# ServoDrivers.net
KiCad netlist of a schematic drawn in Altium Designer
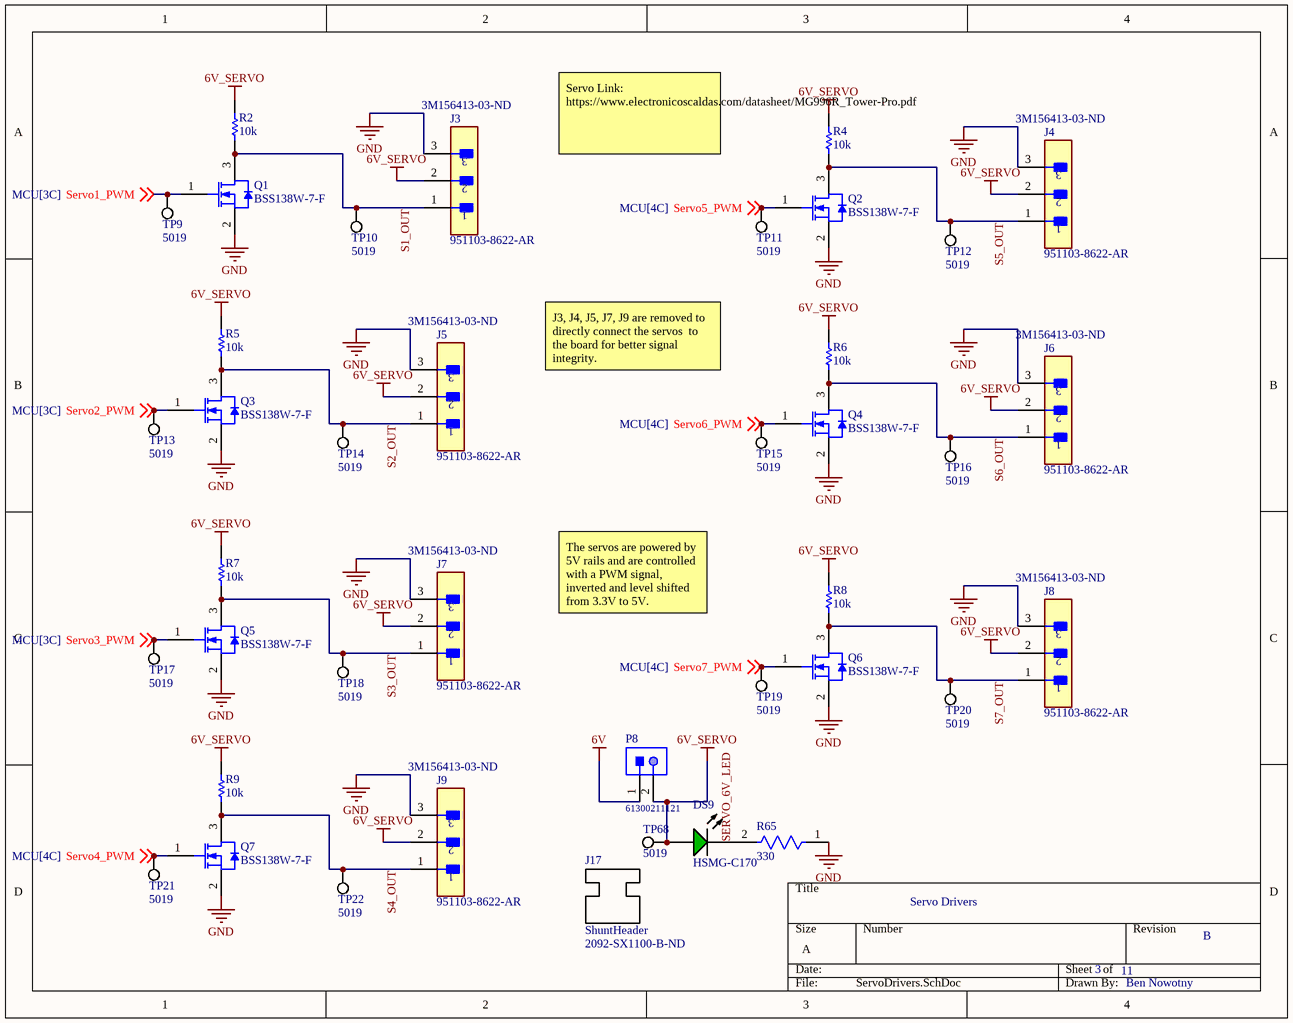
[diagram p0: ServoDrivers.SchDoc]

(export (version "E")
  (design (tool "Eeschema 10.0.6"))
  (components
    (comp (ref "DS9")
      (value "HSMG-C170")
      (footprint "AVAG-HSMX-C170_V")
      (description "Chip LED, Green, 2.2 V, -40 to 85 degC, 2-Pin SMD, Pb-Free, Tape and Reel")
      (fields (field (name "MANUFACTURER") "Avago"))
      (libsource (lib "Altium Content Vault") (part "LED_GREEN_A1K2-2"))
    )
    (comp (ref "J3")
      (value "951103-8622-AR")
      (footprint "FP-951103-8622-AR-MFG")
      (description "CONN HEADER VERT 3POS 2MM")
      (fields
        (field (name "OCTOPART") "https://octopart.com/951103-8622-ar-3m-14400669")
        (field (name "MANUFACTURER") "3M")
        (field (name "SUPPLIER PART NUMBER 1") "3M156413-03-ND")
      )
      (libsource (lib "Altium Content Vault") (part "0d3f023dd272f625e17a2be33dea85f"))
    )
    (comp (ref "J4")
      (value "951103-8622-AR")
      (footprint "FP-951103-8622-AR-MFG")
      (description "CONN HEADER VERT 3POS 2MM")
      (fields
        (field (name "OCTOPART") "https://octopart.com/951103-8622-ar-3m-14400669")
        (field (name "MANUFACTURER") "3M")
        (field (name "SUPPLIER PART NUMBER 1") "3M156413-03-ND")
      )
      (libsource (lib "Altium Content Vault") (part "0d3f023dd272f625e17a2be33dea85f"))
    )
    (comp (ref "J5")
      (value "951103-8622-AR")
      (footprint "FP-951103-8622-AR-MFG")
      (description "CONN HEADER VERT 3POS 2MM")
      (fields
        (field (name "OCTOPART") "https://octopart.com/951103-8622-ar-3m-14400669")
        (field (name "MANUFACTURER") "3M")
        (field (name "SUPPLIER PART NUMBER 1") "3M156413-03-ND")
      )
      (libsource (lib "Altium Content Vault") (part "0d3f023dd272f625e17a2be33dea85f"))
    )
    (comp (ref "J6")
      (value "951103-8622-AR")
      (footprint "FP-951103-8622-AR-MFG")
      (description "CONN HEADER VERT 3POS 2MM")
      (fields
        (field (name "OCTOPART") "https://octopart.com/951103-8622-ar-3m-14400669")
        (field (name "MANUFACTURER") "3M")
        (field (name "SUPPLIER PART NUMBER 1") "3M156413-03-ND")
      )
      (libsource (lib "Altium Content Vault") (part "0d3f023dd272f625e17a2be33dea85f"))
    )
    (comp (ref "J7")
      (value "951103-8622-AR")
      (footprint "FP-951103-8622-AR-MFG")
      (description "CONN HEADER VERT 3POS 2MM")
      (fields
        (field (name "OCTOPART") "https://octopart.com/951103-8622-ar-3m-14400669")
        (field (name "MANUFACTURER") "3M")
        (field (name "SUPPLIER PART NUMBER 1") "3M156413-03-ND")
      )
      (libsource (lib "Altium Content Vault") (part "0d3f023dd272f625e17a2be33dea85f"))
    )
    (comp (ref "J8")
      (value "951103-8622-AR")
      (footprint "FP-951103-8622-AR-MFG")
      (description "CONN HEADER VERT 3POS 2MM")
      (fields
        (field (name "OCTOPART") "https://octopart.com/951103-8622-ar-3m-14400669")
        (field (name "MANUFACTURER") "3M")
        (field (name "SUPPLIER PART NUMBER 1") "3M156413-03-ND")
      )
      (libsource (lib "Altium Content Vault") (part "0d3f023dd272f625e17a2be33dea85f"))
    )
    (comp (ref "J9")
      (value "951103-8622-AR")
      (footprint "FP-951103-8622-AR-MFG")
      (description "CONN HEADER VERT 3POS 2MM")
      (fields
        (field (name "OCTOPART") "https://octopart.com/951103-8622-ar-3m-14400669")
        (field (name "MANUFACTURER") "3M")
        (field (name "SUPPLIER PART NUMBER 1") "3M156413-03-ND")
      )
      (libsource (lib "Altium Content Vault") (part "0d3f023dd272f625e17a2be33dea85f"))
    )
    (comp (ref "J17")
      (value "ShuntHeader")
      (description "Conn Mini Shunt 2 POS 2.54mm Black Cable Mount")
      (fields
        (field (name "MANUFACTURER") "Kycon")
        (field (name "MANUFACTURER PART NUMBER") "SX1100-B")
        (field (name "SUPPLIER PART NUMBER 1") "2092-SX1100-B-ND")
      )
      (libsource (lib "CustomSchematics") (part "ShuntHeader"))
    )
    (comp (ref "P8")
      (value "61300211121")
      (footprint "61300211121")
      (description "THT Vertical Pin Header WR-PHD, Pitch 2.54 mm, Single Row, 2 pins")
      (fields (field (name "MANUFACTURER") "Wurth Elektronik") (field (name "PUBLISHER") "WurthElektronik"))
      (libsource (lib "Altium Content Vault") (part "WE-CN-1P-M-R2"))
    )
    (comp (ref "Q1")
      (value "BSS138W-7-F")
      (footprint "DIOD-SOT323-3_V")
      (fields (field (name "MANUFACTURER") "DiodesIncorporated") (field (name "VOLTAGE") "50V"))
      (libsource (lib "Altium Content Vault") (part "NEMOS-GSD-3"))
    )
    (comp (ref "Q2")
      (value "BSS138W-7-F")
      (footprint "DIOD-SOT323-3_V")
      (fields (field (name "MANUFACTURER") "DiodesIncorporated") (field (name "VOLTAGE") "50V"))
      (libsource (lib "Altium Content Vault") (part "NEMOS-GSD-3"))
    )
    (comp (ref "Q3")
      (value "BSS138W-7-F")
      (footprint "DIOD-SOT323-3_V")
      (fields (field (name "MANUFACTURER") "DiodesIncorporated") (field (name "VOLTAGE") "50V"))
      (libsource (lib "Altium Content Vault") (part "NEMOS-GSD-3"))
    )
    (comp (ref "Q4")
      (value "BSS138W-7-F")
      (footprint "DIOD-SOT323-3_V")
      (fields (field (name "MANUFACTURER") "DiodesIncorporated") (field (name "VOLTAGE") "50V"))
      (libsource (lib "Altium Content Vault") (part "NEMOS-GSD-3"))
    )
    (comp (ref "Q5")
      (value "BSS138W-7-F")
      (footprint "DIOD-SOT323-3_V")
      (fields (field (name "MANUFACTURER") "DiodesIncorporated") (field (name "VOLTAGE") "50V"))
      (libsource (lib "Altium Content Vault") (part "NEMOS-GSD-3"))
    )
    (comp (ref "Q6")
      (value "BSS138W-7-F")
      (footprint "DIOD-SOT323-3_V")
      (fields (field (name "MANUFACTURER") "DiodesIncorporated") (field (name "VOLTAGE") "50V"))
      (libsource (lib "Altium Content Vault") (part "NEMOS-GSD-3"))
    )
    (comp (ref "Q7")
      (value "BSS138W-7-F")
      (footprint "DIOD-SOT323-3_V")
      (fields (field (name "MANUFACTURER") "DiodesIncorporated") (field (name "VOLTAGE") "50V"))
      (libsource (lib "Altium Content Vault") (part "NEMOS-GSD-3"))
    )
    (comp (ref "R2")
      (value "10k")
      (footprint "RESC2013X60X35NL10T20")
      (description "Chip Resistor, 10 KOhm, +/- 1%, 0.125 W, -55 to 155 degC, 0805 (2012 Metric), RoHS, Tape and Reel")
      (fields
        (field (name "MANUFACTURER") "Yageo")
        (field (name "MANUFACTURER PART NUMBER") "RC0805FR-0710KL")
      )
      (libsource (lib "Altium Content Vault") (part "RES-2"))
    )
    (comp (ref "R4")
      (value "10k")
      (footprint "RESC2013X60X35NL10T20")
      (description "Chip Resistor, 10 KOhm, +/- 1%, 0.125 W, -55 to 155 degC, 0805 (2012 Metric), RoHS, Tape and Reel")
      (fields
        (field (name "MANUFACTURER") "Yageo")
        (field (name "MANUFACTURER PART NUMBER") "RC0805FR-0710KL")
      )
      (libsource (lib "Altium Content Vault") (part "RES-2"))
    )
    (comp (ref "R5")
      (value "10k")
      (footprint "RESC2013X60X35NL10T20")
      (description "Chip Resistor, 10 KOhm, +/- 1%, 0.125 W, -55 to 155 degC, 0805 (2012 Metric), RoHS, Tape and Reel")
      (fields
        (field (name "MANUFACTURER") "Yageo")
        (field (name "MANUFACTURER PART NUMBER") "RC0805FR-0710KL")
      )
      (libsource (lib "Altium Content Vault") (part "RES-2"))
    )
    (comp (ref "R6")
      (value "10k")
      (footprint "RESC2013X60X35NL10T20")
      (description "Chip Resistor, 10 KOhm, +/- 1%, 0.125 W, -55 to 155 degC, 0805 (2012 Metric), RoHS, Tape and Reel")
      (fields
        (field (name "MANUFACTURER") "Yageo")
        (field (name "MANUFACTURER PART NUMBER") "RC0805FR-0710KL")
      )
      (libsource (lib "Altium Content Vault") (part "RES-2"))
    )
    (comp (ref "R7")
      (value "10k")
      (footprint "RESC2013X60X35NL10T20")
      (description "Chip Resistor, 10 KOhm, +/- 1%, 0.125 W, -55 to 155 degC, 0805 (2012 Metric), RoHS, Tape and Reel")
      (fields
        (field (name "MANUFACTURER") "Yageo")
        (field (name "MANUFACTURER PART NUMBER") "RC0805FR-0710KL")
      )
      (libsource (lib "Altium Content Vault") (part "RES-2"))
    )
    (comp (ref "R8")
      (value "10k")
      (footprint "RESC2013X60X35NL10T20")
      (description "Chip Resistor, 10 KOhm, +/- 1%, 0.125 W, -55 to 155 degC, 0805 (2012 Metric), RoHS, Tape and Reel")
      (fields
        (field (name "MANUFACTURER") "Yageo")
        (field (name "MANUFACTURER PART NUMBER") "RC0805FR-0710KL")
      )
      (libsource (lib "Altium Content Vault") (part "RES-2"))
    )
    (comp (ref "R9")
      (value "10k")
      (footprint "RESC2013X60X35NL10T20")
      (description "Chip Resistor, 10 KOhm, +/- 1%, 0.125 W, -55 to 155 degC, 0805 (2012 Metric), RoHS, Tape and Reel")
      (fields
        (field (name "MANUFACTURER") "Yageo")
        (field (name "MANUFACTURER PART NUMBER") "RC0805FR-0710KL")
      )
      (libsource (lib "Altium Content Vault") (part "RES-2"))
    )
    (comp (ref "R65")
      (value "330")
      (footprint "FP-CRCW0805-e3-MFG")
      (description "RES Thick Film, 330Ω, 1%, 0.125W, 100ppm/°C, 0805")
      (fields (field (name "TOLERANCE") "1%") (field (name "MANUFACTURER") "Vishay"))
      (libsource (lib "Altium Content Vault") (part "1029c3af85768c4190bb7ad29bc67b5"))
    )
    (comp (ref "TP9")
      (value "5019")
      (footprint "KSTN-5019_V")
      (description "Test Point, 1 Position SMD, RoHS, Tape and Reel")
      (fields (field (name "MANUFACTURER") "Keystone Electronics"))
      (libsource (lib "Altium Content Vault") (part "TESTPOINT_WHITE"))
    )
    (comp (ref "TP10")
      (value "5019")
      (footprint "KSTN-5019_V")
      (description "Test Point, 1 Position SMD, RoHS, Tape and Reel")
      (fields (field (name "MANUFACTURER") "Keystone Electronics"))
      (libsource (lib "Altium Content Vault") (part "TESTPOINT_WHITE"))
    )
    (comp (ref "TP11")
      (value "5019")
      (footprint "KSTN-5019_V")
      (description "Test Point, 1 Position SMD, RoHS, Tape and Reel")
      (fields (field (name "MANUFACTURER") "Keystone Electronics"))
      (libsource (lib "Altium Content Vault") (part "TESTPOINT_WHITE"))
    )
    (comp (ref "TP12")
      (value "5019")
      (footprint "KSTN-5019_V")
      (description "Test Point, 1 Position SMD, RoHS, Tape and Reel")
      (fields (field (name "MANUFACTURER") "Keystone Electronics"))
      (libsource (lib "Altium Content Vault") (part "TESTPOINT_WHITE"))
    )
    (comp (ref "TP13")
      (value "5019")
      (footprint "KSTN-5019_V")
      (description "Test Point, 1 Position SMD, RoHS, Tape and Reel")
      (fields (field (name "MANUFACTURER") "Keystone Electronics"))
      (libsource (lib "Altium Content Vault") (part "TESTPOINT_WHITE"))
    )
    (comp (ref "TP14")
      (value "5019")
      (footprint "KSTN-5019_V")
      (description "Test Point, 1 Position SMD, RoHS, Tape and Reel")
      (fields (field (name "MANUFACTURER") "Keystone Electronics"))
      (libsource (lib "Altium Content Vault") (part "TESTPOINT_WHITE"))
    )
    (comp (ref "TP15")
      (value "5019")
      (footprint "KSTN-5019_V")
      (description "Test Point, 1 Position SMD, RoHS, Tape and Reel")
      (fields (field (name "MANUFACTURER") "Keystone Electronics"))
      (libsource (lib "Altium Content Vault") (part "TESTPOINT_WHITE"))
    )
    (comp (ref "TP16")
      (value "5019")
      (footprint "KSTN-5019_V")
      (description "Test Point, 1 Position SMD, RoHS, Tape and Reel")
      (fields (field (name "MANUFACTURER") "Keystone Electronics"))
      (libsource (lib "Altium Content Vault") (part "TESTPOINT_WHITE"))
    )
    (comp (ref "TP17")
      (value "5019")
      (footprint "KSTN-5019_V")
      (description "Test Point, 1 Position SMD, RoHS, Tape and Reel")
      (fields (field (name "MANUFACTURER") "Keystone Electronics"))
      (libsource (lib "Altium Content Vault") (part "TESTPOINT_WHITE"))
    )
    (comp (ref "TP18")
      (value "5019")
      (footprint "KSTN-5019_V")
      (description "Test Point, 1 Position SMD, RoHS, Tape and Reel")
      (fields (field (name "MANUFACTURER") "Keystone Electronics"))
      (libsource (lib "Altium Content Vault") (part "TESTPOINT_WHITE"))
    )
    (comp (ref "TP19")
      (value "5019")
      (footprint "KSTN-5019_V")
      (description "Test Point, 1 Position SMD, RoHS, Tape and Reel")
      (fields (field (name "MANUFACTURER") "Keystone Electronics"))
      (libsource (lib "Altium Content Vault") (part "TESTPOINT_WHITE"))
    )
    (comp (ref "TP20")
      (value "5019")
      (footprint "KSTN-5019_V")
      (description "Test Point, 1 Position SMD, RoHS, Tape and Reel")
      (fields (field (name "MANUFACTURER") "Keystone Electronics"))
      (libsource (lib "Altium Content Vault") (part "TESTPOINT_WHITE"))
    )
    (comp (ref "TP21")
      (value "5019")
      (footprint "KSTN-5019_V")
      (description "Test Point, 1 Position SMD, RoHS, Tape and Reel")
      (fields (field (name "MANUFACTURER") "Keystone Electronics"))
      (libsource (lib "Altium Content Vault") (part "TESTPOINT_WHITE"))
    )
    (comp (ref "TP22")
      (value "5019")
      (footprint "KSTN-5019_V")
      (description "Test Point, 1 Position SMD, RoHS, Tape and Reel")
      (fields (field (name "MANUFACTURER") "Keystone Electronics"))
      (libsource (lib "Altium Content Vault") (part "TESTPOINT_WHITE"))
    )
    (comp (ref "TP68")
      (value "5019")
      (footprint "KSTN-5019_V")
      (description "Test Point, 1 Position SMD, RoHS, Tape and Reel")
      (fields (field (name "MANUFACTURER") "Keystone Electronics"))
      (libsource (lib "Altium Content Vault") (part "TESTPOINT_WHITE"))
    )
  )
  (nets
    (net (code "1") (name "/S1_OUT") (class "Default")
      (node (ref "J3") (pin "1") (pinfunction "1_1") (pintype "passive"))
      (node (ref "Q1") (pin "3") (pinfunction "D_3") (pintype "passive"))
      (node (ref "R2") (pin "1") (pinfunction "1_1") (pintype "passive"))
      (node (ref "TP10") (pin "1") (pinfunction "1_1") (pintype "passive"))
    )
    (net (code "2") (name "/S2_OUT") (class "Default")
      (node (ref "J5") (pin "1") (pinfunction "1_1") (pintype "passive"))
      (node (ref "Q3") (pin "3") (pinfunction "D_3") (pintype "passive"))
      (node (ref "R5") (pin "1") (pinfunction "1_1") (pintype "passive"))
      (node (ref "TP14") (pin "1") (pinfunction "1_1") (pintype "passive"))
    )
    (net (code "3") (name "/S3_OUT") (class "Default")
      (node (ref "J7") (pin "1") (pinfunction "1_1") (pintype "passive"))
      (node (ref "Q5") (pin "3") (pinfunction "D_3") (pintype "passive"))
      (node (ref "R7") (pin "1") (pinfunction "1_1") (pintype "passive"))
      (node (ref "TP18") (pin "1") (pinfunction "1_1") (pintype "passive"))
    )
    (net (code "4") (name "/S4_OUT") (class "Default")
      (node (ref "J9") (pin "1") (pinfunction "1_1") (pintype "passive"))
      (node (ref "Q7") (pin "3") (pinfunction "D_3") (pintype "passive"))
      (node (ref "R9") (pin "1") (pinfunction "1_1") (pintype "passive"))
      (node (ref "TP22") (pin "1") (pinfunction "1_1") (pintype "passive"))
    )
    (net (code "5") (name "/S5_OUT") (class "Default")
      (node (ref "J4") (pin "1") (pinfunction "1_1") (pintype "passive"))
      (node (ref "Q2") (pin "3") (pinfunction "D_3") (pintype "passive"))
      (node (ref "R4") (pin "1") (pinfunction "1_1") (pintype "passive"))
      (node (ref "TP12") (pin "1") (pinfunction "1_1") (pintype "passive"))
    )
    (net (code "6") (name "/S6_OUT") (class "Default")
      (node (ref "J6") (pin "1") (pinfunction "1_1") (pintype "passive"))
      (node (ref "Q4") (pin "3") (pinfunction "D_3") (pintype "passive"))
      (node (ref "R6") (pin "1") (pinfunction "1_1") (pintype "passive"))
      (node (ref "TP16") (pin "1") (pinfunction "1_1") (pintype "passive"))
    )
    (net (code "7") (name "/S7_OUT") (class "Default")
      (node (ref "J8") (pin "1") (pinfunction "1_1") (pintype "passive"))
      (node (ref "Q6") (pin "3") (pinfunction "D_3") (pintype "passive"))
      (node (ref "R8") (pin "1") (pinfunction "1_1") (pintype "passive"))
      (node (ref "TP20") (pin "1") (pinfunction "1_1") (pintype "passive"))
    )
    (net (code "8") (name "/SERVO_6V_LED") (class "Default")
      (node (ref "DS9") (pin "2") (pinfunction "K_2") (pintype "passive"))
      (node (ref "R65") (pin "2") (pinfunction "2_2") (pintype "passive"))
    )
    (net (code "9") (name "6V") (class "Default")
      (node (ref "P8") (pin "1") (pinfunction "1_1") (pintype "passive"))
    )
    (net (code "10") (name "6V_SERVO") (class "Default")
      (node (ref "DS9") (pin "1") (pinfunction "A_1") (pintype "passive"))
      (node (ref "J3") (pin "2") (pinfunction "2_2") (pintype "passive"))
      (node (ref "J4") (pin "2") (pinfunction "2_2") (pintype "passive"))
      (node (ref "J5") (pin "2") (pinfunction "2_2") (pintype "passive"))
      (node (ref "J6") (pin "2") (pinfunction "2_2") (pintype "passive"))
      (node (ref "J7") (pin "2") (pinfunction "2_2") (pintype "passive"))
      (node (ref "J8") (pin "2") (pinfunction "2_2") (pintype "passive"))
      (node (ref "J9") (pin "2") (pinfunction "2_2") (pintype "passive"))
      (node (ref "P8") (pin "2") (pinfunction "2_2") (pintype "passive"))
      (node (ref "R2") (pin "2") (pinfunction "2_2") (pintype "passive"))
      (node (ref "R4") (pin "2") (pinfunction "2_2") (pintype "passive"))
      (node (ref "R5") (pin "2") (pinfunction "2_2") (pintype "passive"))
      (node (ref "R6") (pin "2") (pinfunction "2_2") (pintype "passive"))
      (node (ref "R7") (pin "2") (pinfunction "2_2") (pintype "passive"))
      (node (ref "R8") (pin "2") (pinfunction "2_2") (pintype "passive"))
      (node (ref "R9") (pin "2") (pinfunction "2_2") (pintype "passive"))
      (node (ref "TP68") (pin "1") (pinfunction "1_1") (pintype "passive"))
    )
    (net (code "11") (name "GND") (class "Default")
      (node (ref "J3") (pin "3") (pinfunction "3_3") (pintype "passive"))
      (node (ref "J4") (pin "3") (pinfunction "3_3") (pintype "passive"))
      (node (ref "J5") (pin "3") (pinfunction "3_3") (pintype "passive"))
      (node (ref "J6") (pin "3") (pinfunction "3_3") (pintype "passive"))
      (node (ref "J7") (pin "3") (pinfunction "3_3") (pintype "passive"))
      (node (ref "J8") (pin "3") (pinfunction "3_3") (pintype "passive"))
      (node (ref "J9") (pin "3") (pinfunction "3_3") (pintype "passive"))
      (node (ref "Q1") (pin "2") (pinfunction "S_2") (pintype "passive"))
      (node (ref "Q2") (pin "2") (pinfunction "S_2") (pintype "passive"))
      (node (ref "Q3") (pin "2") (pinfunction "S_2") (pintype "passive"))
      (node (ref "Q4") (pin "2") (pinfunction "S_2") (pintype "passive"))
      (node (ref "Q5") (pin "2") (pinfunction "S_2") (pintype "passive"))
      (node (ref "Q6") (pin "2") (pinfunction "S_2") (pintype "passive"))
      (node (ref "Q7") (pin "2") (pinfunction "S_2") (pintype "passive"))
      (node (ref "R65") (pin "1") (pinfunction "1_1") (pintype "passive"))
    )
    (net (code "12") (name "Servo1_PWM") (class "Default")
      (node (ref "Q1") (pin "1") (pinfunction "G_1") (pintype "passive"))
      (node (ref "TP9") (pin "1") (pinfunction "1_1") (pintype "passive"))
    )
    (net (code "13") (name "Servo2_PWM") (class "Default")
      (node (ref "Q3") (pin "1") (pinfunction "G_1") (pintype "passive"))
      (node (ref "TP13") (pin "1") (pinfunction "1_1") (pintype "passive"))
    )
    (net (code "14") (name "Servo3_PWM") (class "Default")
      (node (ref "Q5") (pin "1") (pinfunction "G_1") (pintype "passive"))
      (node (ref "TP17") (pin "1") (pinfunction "1_1") (pintype "passive"))
    )
    (net (code "15") (name "Servo4_PWM") (class "Default")
      (node (ref "Q7") (pin "1") (pinfunction "G_1") (pintype "passive"))
      (node (ref "TP21") (pin "1") (pinfunction "1_1") (pintype "passive"))
    )
    (net (code "16") (name "Servo5_PWM") (class "Default")
      (node (ref "Q2") (pin "1") (pinfunction "G_1") (pintype "passive"))
      (node (ref "TP11") (pin "1") (pinfunction "1_1") (pintype "passive"))
    )
    (net (code "17") (name "Servo6_PWM") (class "Default")
      (node (ref "Q4") (pin "1") (pinfunction "G_1") (pintype "passive"))
      (node (ref "TP15") (pin "1") (pinfunction "1_1") (pintype "passive"))
    )
    (net (code "18") (name "Servo7_PWM") (class "Default")
      (node (ref "Q6") (pin "1") (pinfunction "G_1") (pintype "passive"))
      (node (ref "TP19") (pin "1") (pinfunction "1_1") (pintype "passive"))
    )
  )
)
